# Board.net
KiCad netlist of a schematic drawn in EAGLE
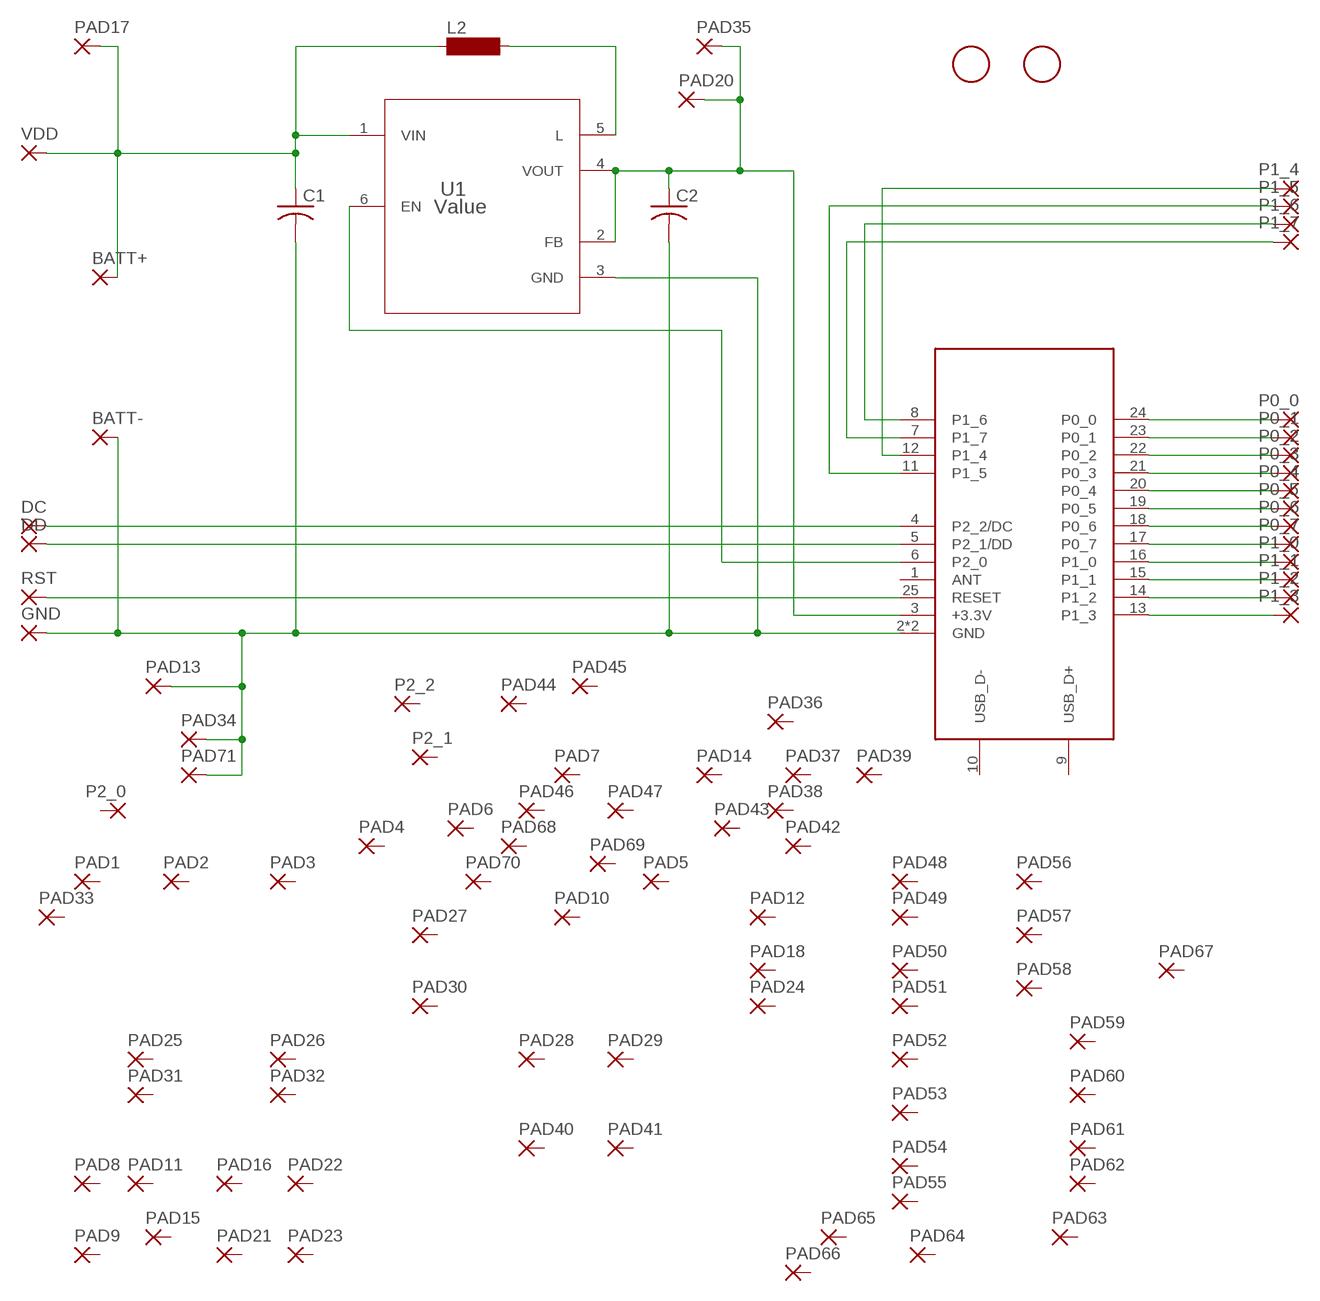
[diagram p0: schematic, sheet 1]

(export (version "E")
  (design (tool "Eeschema 10.0.6"))
  (components
    (comp (ref "BATT+")
      (value "1,6/0,9")
      (footprint "eagle-import:1,6_0,9")
      (libsource (lib "eagle-import") (part "1,6/0,9"))
    )
    (comp (ref "BATT-")
      (value "1,6/0,9")
      (footprint "eagle-import:1,6_0,9")
      (libsource (lib "eagle-import") (part "1,6/0,9"))
    )
    (comp (ref "C1")
      (value "C-USC0603")
      (footprint "eagle-import:C0603")
      (libsource (lib "eagle-import") (part "C-USC0603"))
    )
    (comp (ref "C2")
      (value "C-USC0603")
      (footprint "eagle-import:C0603")
      (libsource (lib "eagle-import") (part "C-USC0603"))
    )
    (comp (ref "DC")
      (value "SMD2")
      (footprint "eagle-import:SMD1,27-2,54")
      (libsource (lib "eagle-import") (part "SMD2"))
    )
    (comp (ref "DD")
      (value "SMD2")
      (footprint "eagle-import:SMD1,27-2,54")
      (libsource (lib "eagle-import") (part "SMD2"))
    )
    (comp (ref "E1")
      (value "CC2540-MODULE-BOARD")
      (footprint "eagle-import:24X15_BOARD")
      (libsource (lib "eagle-import") (part "CC2540-MODULE-BOARD"))
    )
    (comp (ref "GND")
      (value "SMD2")
      (footprint "eagle-import:SMD1,27-2,54")
      (libsource (lib "eagle-import") (part "SMD2"))
    )
    (comp (ref "L2")
      (value "SM-NE29")
      (footprint "eagle-import:SM-NE29")
      (libsource (lib "eagle-import") (part "SM-NE29"))
    )
    (comp (ref "P0_0")
      (value "1,6/0,9")
      (footprint "eagle-import:1,6_0,9")
      (libsource (lib "eagle-import") (part "1,6/0,9"))
    )
    (comp (ref "P0_1")
      (value "1,6/0,9")
      (footprint "eagle-import:1,6_0,9")
      (libsource (lib "eagle-import") (part "1,6/0,9"))
    )
    (comp (ref "P0_2")
      (value "1,6/0,9")
      (footprint "eagle-import:1,6_0,9")
      (libsource (lib "eagle-import") (part "1,6/0,9"))
    )
    (comp (ref "P0_3")
      (value "1,6/0,9")
      (footprint "eagle-import:1,6_0,9")
      (libsource (lib "eagle-import") (part "1,6/0,9"))
    )
    (comp (ref "P0_4")
      (value "1,6/0,9")
      (footprint "eagle-import:1,6_0,9")
      (libsource (lib "eagle-import") (part "1,6/0,9"))
    )
    (comp (ref "P0_5")
      (value "1,6/0,9")
      (footprint "eagle-import:1,6_0,9")
      (libsource (lib "eagle-import") (part "1,6/0,9"))
    )
    (comp (ref "P0_6")
      (value "1,6/0,9")
      (footprint "eagle-import:1,6_0,9")
      (libsource (lib "eagle-import") (part "1,6/0,9"))
    )
    (comp (ref "P0_7")
      (value "1,6/0,9")
      (footprint "eagle-import:1,6_0,9")
      (libsource (lib "eagle-import") (part "1,6/0,9"))
    )
    (comp (ref "P1_0")
      (value "1,6/0,9")
      (footprint "eagle-import:1,6_0,9")
      (libsource (lib "eagle-import") (part "1,6/0,9"))
    )
    (comp (ref "P1_1")
      (value "1,6/0,9")
      (footprint "eagle-import:1,6_0,9")
      (libsource (lib "eagle-import") (part "1,6/0,9"))
    )
    (comp (ref "P1_2")
      (value "1,6/0,9")
      (footprint "eagle-import:1,6_0,9")
      (libsource (lib "eagle-import") (part "1,6/0,9"))
    )
    (comp (ref "P1_3")
      (value "1,6/0,9")
      (footprint "eagle-import:1,6_0,9")
      (libsource (lib "eagle-import") (part "1,6/0,9"))
    )
    (comp (ref "P1_4")
      (value "1,6/0,9")
      (footprint "eagle-import:1,6_0,9")
      (libsource (lib "eagle-import") (part "1,6/0,9"))
    )
    (comp (ref "P1_5")
      (value "1,6/0,9")
      (footprint "eagle-import:1,6_0,9")
      (libsource (lib "eagle-import") (part "1,6/0,9"))
    )
    (comp (ref "P1_6")
      (value "1,6/0,9")
      (footprint "eagle-import:1,6_0,9")
      (libsource (lib "eagle-import") (part "1,6/0,9"))
    )
    (comp (ref "P1_7")
      (value "1,6/0,9")
      (footprint "eagle-import:1,6_0,9")
      (libsource (lib "eagle-import") (part "1,6/0,9"))
    )
    (comp (ref "P2_0")
      (value "1,6/0,9")
      (footprint "eagle-import:1,6_0,9")
      (libsource (lib "eagle-import") (part "1,6/0,9"))
    )
    (comp (ref "P2_1")
      (value "1,6/0,9")
      (footprint "eagle-import:1,6_0,9")
      (libsource (lib "eagle-import") (part "1,6/0,9"))
    )
    (comp (ref "P2_2")
      (value "1,6/0,9")
      (footprint "eagle-import:1,6_0,9")
      (libsource (lib "eagle-import") (part "1,6/0,9"))
    )
    (comp (ref "PAD1")
      (value "1,6/0,9")
      (footprint "eagle-import:1,6_0,9")
      (libsource (lib "eagle-import") (part "1,6/0,9"))
    )
    (comp (ref "PAD2")
      (value "1,6/0,9")
      (footprint "eagle-import:1,6_0,9")
      (libsource (lib "eagle-import") (part "1,6/0,9"))
    )
    (comp (ref "PAD3")
      (value "1,6/0,9")
      (footprint "eagle-import:1,6_0,9")
      (libsource (lib "eagle-import") (part "1,6/0,9"))
    )
    (comp (ref "PAD4")
      (value "1,6/0,9")
      (footprint "eagle-import:1,6_0,9")
      (libsource (lib "eagle-import") (part "1,6/0,9"))
    )
    (comp (ref "PAD5")
      (value "1,6/0,9")
      (footprint "eagle-import:1,6_0,9")
      (libsource (lib "eagle-import") (part "1,6/0,9"))
    )
    (comp (ref "PAD6")
      (value "1,6/0,9")
      (footprint "eagle-import:1,6_0,9")
      (libsource (lib "eagle-import") (part "1,6/0,9"))
    )
    (comp (ref "PAD7")
      (value "1,6/0,9")
      (footprint "eagle-import:1,6_0,9")
      (libsource (lib "eagle-import") (part "1,6/0,9"))
    )
    (comp (ref "PAD8")
      (value "1,6/0,9")
      (footprint "eagle-import:1,6_0,9")
      (libsource (lib "eagle-import") (part "1,6/0,9"))
    )
    (comp (ref "PAD9")
      (value "1,6/0,9")
      (footprint "eagle-import:1,6_0,9")
      (libsource (lib "eagle-import") (part "1,6/0,9"))
    )
    (comp (ref "PAD10")
      (value "1,6/0,9")
      (footprint "eagle-import:1,6_0,9")
      (libsource (lib "eagle-import") (part "1,6/0,9"))
    )
    (comp (ref "PAD11")
      (value "1,6/0,9")
      (footprint "eagle-import:1,6_0,9")
      (libsource (lib "eagle-import") (part "1,6/0,9"))
    )
    (comp (ref "PAD12")
      (value "1,6/0,9")
      (footprint "eagle-import:1,6_0,9")
      (libsource (lib "eagle-import") (part "1,6/0,9"))
    )
    (comp (ref "PAD13")
      (value "1,6/0,9")
      (footprint "eagle-import:1,6_0,9")
      (libsource (lib "eagle-import") (part "1,6/0,9"))
    )
    (comp (ref "PAD14")
      (value "1,6/0,9")
      (footprint "eagle-import:1,6_0,9")
      (libsource (lib "eagle-import") (part "1,6/0,9"))
    )
    (comp (ref "PAD15")
      (value "1,6/0,9")
      (footprint "eagle-import:1,6_0,9")
      (libsource (lib "eagle-import") (part "1,6/0,9"))
    )
    (comp (ref "PAD16")
      (value "1,6/0,9")
      (footprint "eagle-import:1,6_0,9")
      (libsource (lib "eagle-import") (part "1,6/0,9"))
    )
    (comp (ref "PAD17")
      (value "1,6/0,9")
      (footprint "eagle-import:1,6_0,9")
      (libsource (lib "eagle-import") (part "1,6/0,9"))
    )
    (comp (ref "PAD18")
      (value "1,6/0,9")
      (footprint "eagle-import:1,6_0,9")
      (libsource (lib "eagle-import") (part "1,6/0,9"))
    )
    (comp (ref "PAD20")
      (value "1,6/0,9")
      (footprint "eagle-import:1,6_0,9")
      (libsource (lib "eagle-import") (part "1,6/0,9"))
    )
    (comp (ref "PAD21")
      (value "1,6/0,9")
      (footprint "eagle-import:1,6_0,9")
      (libsource (lib "eagle-import") (part "1,6/0,9"))
    )
    (comp (ref "PAD22")
      (value "1,6/0,9")
      (footprint "eagle-import:1,6_0,9")
      (libsource (lib "eagle-import") (part "1,6/0,9"))
    )
    (comp (ref "PAD23")
      (value "1,6/0,9")
      (footprint "eagle-import:1,6_0,9")
      (libsource (lib "eagle-import") (part "1,6/0,9"))
    )
    (comp (ref "PAD24")
      (value "1,6/0,9")
      (footprint "eagle-import:1,6_0,9")
      (libsource (lib "eagle-import") (part "1,6/0,9"))
    )
    (comp (ref "PAD25")
      (value "1,6/0,9")
      (footprint "eagle-import:1,6_0,9")
      (libsource (lib "eagle-import") (part "1,6/0,9"))
    )
    (comp (ref "PAD26")
      (value "1,6/0,9")
      (footprint "eagle-import:1,6_0,9")
      (libsource (lib "eagle-import") (part "1,6/0,9"))
    )
    (comp (ref "PAD27")
      (value "1,6/0,9")
      (footprint "eagle-import:1,6_0,9")
      (libsource (lib "eagle-import") (part "1,6/0,9"))
    )
    (comp (ref "PAD28")
      (value "1,6/0,9")
      (footprint "eagle-import:1,6_0,9")
      (libsource (lib "eagle-import") (part "1,6/0,9"))
    )
    (comp (ref "PAD29")
      (value "1,6/0,9")
      (footprint "eagle-import:1,6_0,9")
      (libsource (lib "eagle-import") (part "1,6/0,9"))
    )
    (comp (ref "PAD30")
      (value "1,6/0,9")
      (footprint "eagle-import:1,6_0,9")
      (libsource (lib "eagle-import") (part "1,6/0,9"))
    )
    (comp (ref "PAD31")
      (value "1,6/0,9")
      (footprint "eagle-import:1,6_0,9")
      (libsource (lib "eagle-import") (part "1,6/0,9"))
    )
    (comp (ref "PAD32")
      (value "1,6/0,9")
      (footprint "eagle-import:1,6_0,9")
      (libsource (lib "eagle-import") (part "1,6/0,9"))
    )
    (comp (ref "PAD33")
      (value "1,6/0,9")
      (footprint "eagle-import:1,6_0,9")
      (libsource (lib "eagle-import") (part "1,6/0,9"))
    )
    (comp (ref "PAD34")
      (value "1,6/0,9")
      (footprint "eagle-import:1,6_0,9")
      (libsource (lib "eagle-import") (part "1,6/0,9"))
    )
    (comp (ref "PAD35")
      (value "1,6/0,9")
      (footprint "eagle-import:1,6_0,9")
      (libsource (lib "eagle-import") (part "1,6/0,9"))
    )
    (comp (ref "PAD36")
      (value "1,6/0,9")
      (footprint "eagle-import:1,6_0,9")
      (libsource (lib "eagle-import") (part "1,6/0,9"))
    )
    (comp (ref "PAD37")
      (value "1,6/0,9")
      (footprint "eagle-import:1,6_0,9")
      (libsource (lib "eagle-import") (part "1,6/0,9"))
    )
    (comp (ref "PAD38")
      (value "1,6/0,9")
      (footprint "eagle-import:1,6_0,9")
      (libsource (lib "eagle-import") (part "1,6/0,9"))
    )
    (comp (ref "PAD39")
      (value "1,6/0,9")
      (footprint "eagle-import:1,6_0,9")
      (libsource (lib "eagle-import") (part "1,6/0,9"))
    )
    (comp (ref "PAD40")
      (value "1,6/0,9")
      (footprint "eagle-import:1,6_0,9")
      (libsource (lib "eagle-import") (part "1,6/0,9"))
    )
    (comp (ref "PAD41")
      (value "1,6/0,9")
      (footprint "eagle-import:1,6_0,9")
      (libsource (lib "eagle-import") (part "1,6/0,9"))
    )
    (comp (ref "PAD42")
      (value "1,6/0,9")
      (footprint "eagle-import:1,6_0,9")
      (libsource (lib "eagle-import") (part "1,6/0,9"))
    )
    (comp (ref "PAD43")
      (value "1,6/0,9")
      (footprint "eagle-import:1,6_0,9")
      (libsource (lib "eagle-import") (part "1,6/0,9"))
    )
    (comp (ref "PAD44")
      (value "1,6/0,9")
      (footprint "eagle-import:1,6_0,9")
      (libsource (lib "eagle-import") (part "1,6/0,9"))
    )
    (comp (ref "PAD45")
      (value "1,6/0,9")
      (footprint "eagle-import:1,6_0,9")
      (libsource (lib "eagle-import") (part "1,6/0,9"))
    )
    (comp (ref "PAD46")
      (value "1,6/0,9")
      (footprint "eagle-import:1,6_0,9")
      (libsource (lib "eagle-import") (part "1,6/0,9"))
    )
    (comp (ref "PAD47")
      (value "1,6/0,9")
      (footprint "eagle-import:1,6_0,9")
      (libsource (lib "eagle-import") (part "1,6/0,9"))
    )
    (comp (ref "PAD48")
      (value "1,6/0,9")
      (footprint "eagle-import:1,6_0,9")
      (libsource (lib "eagle-import") (part "1,6/0,9"))
    )
    (comp (ref "PAD49")
      (value "1,6/0,9")
      (footprint "eagle-import:1,6_0,9")
      (libsource (lib "eagle-import") (part "1,6/0,9"))
    )
    (comp (ref "PAD50")
      (value "1,6/0,9")
      (footprint "eagle-import:1,6_0,9")
      (libsource (lib "eagle-import") (part "1,6/0,9"))
    )
    (comp (ref "PAD51")
      (value "1,6/0,9")
      (footprint "eagle-import:1,6_0,9")
      (libsource (lib "eagle-import") (part "1,6/0,9"))
    )
    (comp (ref "PAD52")
      (value "1,6/0,9")
      (footprint "eagle-import:1,6_0,9")
      (libsource (lib "eagle-import") (part "1,6/0,9"))
    )
    (comp (ref "PAD53")
      (value "1,6/0,9")
      (footprint "eagle-import:1,6_0,9")
      (libsource (lib "eagle-import") (part "1,6/0,9"))
    )
    (comp (ref "PAD54")
      (value "1,6/0,9")
      (footprint "eagle-import:1,6_0,9")
      (libsource (lib "eagle-import") (part "1,6/0,9"))
    )
    (comp (ref "PAD55")
      (value "1,6/0,9")
      (footprint "eagle-import:1,6_0,9")
      (libsource (lib "eagle-import") (part "1,6/0,9"))
    )
    (comp (ref "PAD56")
      (value "1,6/0,9")
      (footprint "eagle-import:1,6_0,9")
      (libsource (lib "eagle-import") (part "1,6/0,9"))
    )
    (comp (ref "PAD57")
      (value "1,6/0,9")
      (footprint "eagle-import:1,6_0,9")
      (libsource (lib "eagle-import") (part "1,6/0,9"))
    )
    (comp (ref "PAD58")
      (value "1,6/0,9")
      (footprint "eagle-import:1,6_0,9")
      (libsource (lib "eagle-import") (part "1,6/0,9"))
    )
    (comp (ref "PAD59")
      (value "1,6/0,9")
      (footprint "eagle-import:1,6_0,9")
      (libsource (lib "eagle-import") (part "1,6/0,9"))
    )
    (comp (ref "PAD60")
      (value "1,6/0,9")
      (footprint "eagle-import:1,6_0,9")
      (libsource (lib "eagle-import") (part "1,6/0,9"))
    )
    (comp (ref "PAD61")
      (value "1,6/0,9")
      (footprint "eagle-import:1,6_0,9")
      (libsource (lib "eagle-import") (part "1,6/0,9"))
    )
    (comp (ref "PAD62")
      (value "1,6/0,9")
      (footprint "eagle-import:1,6_0,9")
      (libsource (lib "eagle-import") (part "1,6/0,9"))
    )
    (comp (ref "PAD63")
      (value "1,6/0,9")
      (footprint "eagle-import:1,6_0,9")
      (libsource (lib "eagle-import") (part "1,6/0,9"))
    )
    (comp (ref "PAD64")
      (value "1,6/0,9")
      (footprint "eagle-import:1,6_0,9")
      (libsource (lib "eagle-import") (part "1,6/0,9"))
    )
    (comp (ref "PAD65")
      (value "1,6/0,9")
      (footprint "eagle-import:1,6_0,9")
      (libsource (lib "eagle-import") (part "1,6/0,9"))
    )
    (comp (ref "PAD66")
      (value "1,6/0,9")
      (footprint "eagle-import:1,6_0,9")
      (libsource (lib "eagle-import") (part "1,6/0,9"))
    )
    (comp (ref "PAD67")
      (value "1,6/0,9")
      (footprint "eagle-import:1,6_0,9")
      (libsource (lib "eagle-import") (part "1,6/0,9"))
    )
    (comp (ref "PAD68")
      (value "1,6/0,9")
      (footprint "eagle-import:1,6_0,9")
      (libsource (lib "eagle-import") (part "1,6/0,9"))
    )
    (comp (ref "PAD69")
      (value "1,6/0,9")
      (footprint "eagle-import:1,6_0,9")
      (libsource (lib "eagle-import") (part "1,6/0,9"))
    )
    (comp (ref "PAD70")
      (value "1,6/0,9")
      (footprint "eagle-import:1,6_0,9")
      (libsource (lib "eagle-import") (part "1,6/0,9"))
    )
    (comp (ref "PAD71")
      (value "1,6/0,9")
      (footprint "eagle-import:1,6_0,9")
      (libsource (lib "eagle-import") (part "1,6/0,9"))
    )
    (comp (ref "RST")
      (value "SMD2")
      (footprint "eagle-import:SMD1,27-2,54")
      (libsource (lib "eagle-import") (part "SMD2"))
    )
    (comp (ref "U$1")
      (value "FIDUCIAL")
      (footprint "eagle-import:FIDUCIAL_1MM")
      (libsource (lib "eagle-import") (part "FIDUCIAL"))
    )
    (comp (ref "U$2")
      (value "FIDUCIAL")
      (footprint "eagle-import:FIDUCIAL_1MM")
      (libsource (lib "eagle-import") (part "FIDUCIAL"))
    )
    (comp (ref "U1")
      (value "Value")
      (footprint "eagle-import:DCK0006A")
      (fields (field (name "MANUFACTURER") "Texas Instruments") (field (name "PARTNUMBER") "TPS61221DCK"))
      (libsource (lib "eagle-import") (part "TPS61221DCKR"))
    )
    (comp (ref "VDD")
      (value "SMD2")
      (footprint "eagle-import:SMD1,27-2,54")
      (libsource (lib "eagle-import") (part "SMD2"))
    )
  )
  (nets
    (net (code "1") (name "Net-(BATT+-P)") (class "Default")
      (node (ref "BATT+") (pin "1") (pinfunction "P_1") (pintype "passive"))
      (node (ref "C1") (pin "1") (pinfunction "1_1") (pintype "passive"))
      (node (ref "L2") (pin "1") (pinfunction "1_1") (pintype "passive"))
      (node (ref "PAD17") (pin "1") (pinfunction "P_1") (pintype "passive"))
      (node (ref "U1") (pin "1") (pinfunction "VIN_1") (pintype "power_in"))
      (node (ref "VDD") (pin "1") (pinfunction "P_1") (pintype "passive"))
    )
    (net (code "2") (name "Net-(BATT--P)") (class "Default")
      (node (ref "BATT-") (pin "1") (pinfunction "P_1") (pintype "passive"))
      (node (ref "C1") (pin "2") (pinfunction "2_2") (pintype "passive"))
      (node (ref "C2") (pin "2") (pinfunction "2_2") (pintype "passive"))
      (node (ref "E1") (pin "2") (pinfunction "GND_2") (pintype "bidirectional"))
      (node (ref "E1") (pin "26") (pinfunction "GND_26") (pintype "bidirectional"))
      (node (ref "GND") (pin "1") (pinfunction "P_1") (pintype "passive"))
      (node (ref "PAD13") (pin "1") (pinfunction "P_1") (pintype "passive"))
      (node (ref "PAD34") (pin "1") (pinfunction "P_1") (pintype "passive"))
      (node (ref "PAD71") (pin "1") (pinfunction "P_1") (pintype "passive"))
      (node (ref "U1") (pin "3") (pinfunction "GND_3") (pintype "power_in"))
    )
    (net (code "3") (name "Net-(DC-P)") (class "Default")
      (node (ref "DC") (pin "1") (pinfunction "P_1") (pintype "passive"))
      (node (ref "E1") (pin "4") (pinfunction "P2_2/DC_4") (pintype "bidirectional"))
    )
    (net (code "4") (name "Net-(DD-P)") (class "Default")
      (node (ref "DD") (pin "1") (pinfunction "P_1") (pintype "passive"))
      (node (ref "E1") (pin "5") (pinfunction "P2_1/DD_5") (pintype "bidirectional"))
    )
    (net (code "5") (name "Net-(E1-+3.3V)") (class "Default")
      (node (ref "C2") (pin "1") (pinfunction "1_1") (pintype "passive"))
      (node (ref "E1") (pin "3") (pinfunction "+3.3V_3") (pintype "bidirectional"))
      (node (ref "PAD20") (pin "1") (pinfunction "P_1") (pintype "passive"))
      (node (ref "PAD35") (pin "1") (pinfunction "P_1") (pintype "passive"))
      (node (ref "U1") (pin "2") (pinfunction "FB_2") (pintype "input"))
      (node (ref "U1") (pin "4") (pinfunction "VOUT_4") (pintype "power_in"))
    )
    (net (code "6") (name "Net-(E1-P0_0)") (class "Default")
      (node (ref "E1") (pin "24") (pinfunction "P0_0_24") (pintype "bidirectional"))
      (node (ref "P0_0") (pin "1") (pinfunction "P_1") (pintype "passive"))
    )
    (net (code "7") (name "Net-(E1-P0_1)") (class "Default")
      (node (ref "E1") (pin "23") (pinfunction "P0_1_23") (pintype "bidirectional"))
      (node (ref "P0_1") (pin "1") (pinfunction "P_1") (pintype "passive"))
    )
    (net (code "8") (name "Net-(E1-P0_2)") (class "Default")
      (node (ref "E1") (pin "22") (pinfunction "P0_2_22") (pintype "bidirectional"))
      (node (ref "P0_2") (pin "1") (pinfunction "P_1") (pintype "passive"))
    )
    (net (code "9") (name "Net-(E1-P0_3)") (class "Default")
      (node (ref "E1") (pin "21") (pinfunction "P0_3_21") (pintype "bidirectional"))
      (node (ref "P0_3") (pin "1") (pinfunction "P_1") (pintype "passive"))
    )
    (net (code "10") (name "Net-(E1-P0_4)") (class "Default")
      (node (ref "E1") (pin "20") (pinfunction "P0_4_20") (pintype "bidirectional"))
      (node (ref "P0_4") (pin "1") (pinfunction "P_1") (pintype "passive"))
    )
    (net (code "11") (name "Net-(E1-P0_5)") (class "Default")
      (node (ref "E1") (pin "19") (pinfunction "P0_5_19") (pintype "bidirectional"))
      (node (ref "P0_5") (pin "1") (pinfunction "P_1") (pintype "passive"))
    )
    (net (code "12") (name "Net-(E1-P0_6)") (class "Default")
      (node (ref "E1") (pin "18") (pinfunction "P0_6_18") (pintype "bidirectional"))
      (node (ref "P0_6") (pin "1") (pinfunction "P_1") (pintype "passive"))
    )
    (net (code "13") (name "Net-(E1-P0_7)") (class "Default")
      (node (ref "E1") (pin "17") (pinfunction "P0_7_17") (pintype "bidirectional"))
      (node (ref "P0_7") (pin "1") (pinfunction "P_1") (pintype "passive"))
    )
    (net (code "14") (name "Net-(E1-P1_0)") (class "Default")
      (node (ref "E1") (pin "16") (pinfunction "P1_0_16") (pintype "bidirectional"))
      (node (ref "P1_0") (pin "1") (pinfunction "P_1") (pintype "passive"))
    )
    (net (code "15") (name "Net-(E1-P1_1)") (class "Default")
      (node (ref "E1") (pin "15") (pinfunction "P1_1_15") (pintype "bidirectional"))
      (node (ref "P1_1") (pin "1") (pinfunction "P_1") (pintype "passive"))
    )
    (net (code "16") (name "Net-(E1-P1_2)") (class "Default")
      (node (ref "E1") (pin "14") (pinfunction "P1_2_14") (pintype "bidirectional"))
      (node (ref "P1_2") (pin "1") (pinfunction "P_1") (pintype "passive"))
    )
    (net (code "17") (name "Net-(E1-P1_3)") (class "Default")
      (node (ref "E1") (pin "13") (pinfunction "P1_3_13") (pintype "bidirectional"))
      (node (ref "P1_3") (pin "1") (pinfunction "P_1") (pintype "passive"))
    )
    (net (code "18") (name "Net-(E1-P1_4)") (class "Default")
      (node (ref "E1") (pin "12") (pinfunction "P1_4_12") (pintype "bidirectional"))
      (node (ref "P1_4") (pin "1") (pinfunction "P_1") (pintype "passive"))
    )
    (net (code "19") (name "Net-(E1-P1_5)") (class "Default")
      (node (ref "E1") (pin "11") (pinfunction "P1_5_11") (pintype "bidirectional"))
      (node (ref "P1_5") (pin "1") (pinfunction "P_1") (pintype "passive"))
    )
    (net (code "20") (name "Net-(E1-P1_6)") (class "Default")
      (node (ref "E1") (pin "8") (pinfunction "P1_6_8") (pintype "bidirectional"))
      (node (ref "P1_6") (pin "1") (pinfunction "P_1") (pintype "passive"))
    )
    (net (code "21") (name "Net-(E1-P1_7)") (class "Default")
      (node (ref "E1") (pin "7") (pinfunction "P1_7_7") (pintype "bidirectional"))
      (node (ref "P1_7") (pin "1") (pinfunction "P_1") (pintype "passive"))
    )
    (net (code "22") (name "Net-(E1-P2_0)") (class "Default")
      (node (ref "E1") (pin "6") (pinfunction "P2_0_6") (pintype "bidirectional"))
      (node (ref "U1") (pin "6") (pinfunction "EN_6") (pintype "input"))
    )
    (net (code "23") (name "Net-(E1-RESET)") (class "Default")
      (node (ref "E1") (pin "25") (pinfunction "RESET_25") (pintype "bidirectional"))
      (node (ref "RST") (pin "1") (pinfunction "P_1") (pintype "passive"))
    )
    (net (code "24") (name "Net-(U1-L)") (class "Default")
      (node (ref "L2") (pin "2") (pinfunction "2_2") (pintype "passive"))
      (node (ref "U1") (pin "5") (pinfunction "L_5") (pintype "passive"))
    )
    (net (code "25") (name "unconnected-(E1-ANT-Pad1)") (class "Default")
      (node (ref "E1") (pin "1") (pinfunction "ANT_1") (pintype "bidirectional"))
    )
    (net (code "26") (name "unconnected-(E1-USB_D+-Pad9)") (class "Default")
      (node (ref "E1") (pin "9") (pinfunction "USB_D+_9") (pintype "bidirectional"))
    )
    (net (code "27") (name "unconnected-(E1-USB_D--Pad10)") (class "Default")
      (node (ref "E1") (pin "10") (pinfunction "USB_D-_10") (pintype "bidirectional"))
    )
    (net (code "28") (name "unconnected-(P2_0-P-Pad1)") (class "Default")
      (node (ref "P2_0") (pin "1") (pinfunction "P_1") (pintype "passive"))
    )
    (net (code "29") (name "unconnected-(P2_1-P-Pad1)") (class "Default")
      (node (ref "P2_1") (pin "1") (pinfunction "P_1") (pintype "passive"))
    )
    (net (code "30") (name "unconnected-(P2_2-P-Pad1)") (class "Default")
      (node (ref "P2_2") (pin "1") (pinfunction "P_1") (pintype "passive"))
    )
    (net (code "31") (name "unconnected-(PAD1-P-Pad1)") (class "Default")
      (node (ref "PAD1") (pin "1") (pinfunction "P_1") (pintype "passive"))
    )
    (net (code "32") (name "unconnected-(PAD2-P-Pad1)") (class "Default")
      (node (ref "PAD2") (pin "1") (pinfunction "P_1") (pintype "passive"))
    )
    (net (code "33") (name "unconnected-(PAD3-P-Pad1)") (class "Default")
      (node (ref "PAD3") (pin "1") (pinfunction "P_1") (pintype "passive"))
    )
    (net (code "34") (name "unconnected-(PAD4-P-Pad1)") (class "Default")
      (node (ref "PAD4") (pin "1") (pinfunction "P_1") (pintype "passive"))
    )
    (net (code "35") (name "unconnected-(PAD5-P-Pad1)") (class "Default")
      (node (ref "PAD5") (pin "1") (pinfunction "P_1") (pintype "passive"))
    )
    (net (code "36") (name "unconnected-(PAD6-P-Pad1)") (class "Default")
      (node (ref "PAD6") (pin "1") (pinfunction "P_1") (pintype "passive"))
    )
    (net (code "37") (name "unconnected-(PAD7-P-Pad1)") (class "Default")
      (node (ref "PAD7") (pin "1") (pinfunction "P_1") (pintype "passive"))
    )
    (net (code "38") (name "unconnected-(PAD8-P-Pad1)") (class "Default")
      (node (ref "PAD8") (pin "1") (pinfunction "P_1") (pintype "passive"))
    )
    (net (code "39") (name "unconnected-(PAD9-P-Pad1)") (class "Default")
      (node (ref "PAD9") (pin "1") (pinfunction "P_1") (pintype "passive"))
    )
    (net (code "40") (name "unconnected-(PAD10-P-Pad1)") (class "Default")
      (node (ref "PAD10") (pin "1") (pinfunction "P_1") (pintype "passive"))
    )
    (net (code "41") (name "unconnected-(PAD11-P-Pad1)") (class "Default")
      (node (ref "PAD11") (pin "1") (pinfunction "P_1") (pintype "passive"))
    )
    (net (code "42") (name "unconnected-(PAD12-P-Pad1)") (class "Default")
      (node (ref "PAD12") (pin "1") (pinfunction "P_1") (pintype "passive"))
    )
    (net (code "43") (name "unconnected-(PAD14-P-Pad1)") (class "Default")
      (node (ref "PAD14") (pin "1") (pinfunction "P_1") (pintype "passive"))
    )
    (net (code "44") (name "unconnected-(PAD15-P-Pad1)") (class "Default")
      (node (ref "PAD15") (pin "1") (pinfunction "P_1") (pintype "passive"))
    )
    (net (code "45") (name "unconnected-(PAD16-P-Pad1)") (class "Default")
      (node (ref "PAD16") (pin "1") (pinfunction "P_1") (pintype "passive"))
    )
    (net (code "46") (name "unconnected-(PAD18-P-Pad1)") (class "Default")
      (node (ref "PAD18") (pin "1") (pinfunction "P_1") (pintype "passive"))
    )
    (net (code "47") (name "unconnected-(PAD21-P-Pad1)") (class "Default")
      (node (ref "PAD21") (pin "1") (pinfunction "P_1") (pintype "passive"))
    )
    (net (code "48") (name "unconnected-(PAD22-P-Pad1)") (class "Default")
      (node (ref "PAD22") (pin "1") (pinfunction "P_1") (pintype "passive"))
    )
    (net (code "49") (name "unconnected-(PAD23-P-Pad1)") (class "Default")
      (node (ref "PAD23") (pin "1") (pinfunction "P_1") (pintype "passive"))
    )
    (net (code "50") (name "unconnected-(PAD24-P-Pad1)") (class "Default")
      (node (ref "PAD24") (pin "1") (pinfunction "P_1") (pintype "passive"))
    )
    (net (code "51") (name "unconnected-(PAD25-P-Pad1)") (class "Default")
      (node (ref "PAD25") (pin "1") (pinfunction "P_1") (pintype "passive"))
    )
    (net (code "52") (name "unconnected-(PAD26-P-Pad1)") (class "Default")
      (node (ref "PAD26") (pin "1") (pinfunction "P_1") (pintype "passive"))
    )
    (net (code "53") (name "unconnected-(PAD27-P-Pad1)") (class "Default")
      (node (ref "PAD27") (pin "1") (pinfunction "P_1") (pintype "passive"))
    )
    (net (code "54") (name "unconnected-(PAD28-P-Pad1)") (class "Default")
      (node (ref "PAD28") (pin "1") (pinfunction "P_1") (pintype "passive"))
    )
    (net (code "55") (name "unconnected-(PAD29-P-Pad1)") (class "Default")
      (node (ref "PAD29") (pin "1") (pinfunction "P_1") (pintype "passive"))
    )
    (net (code "56") (name "unconnected-(PAD30-P-Pad1)") (class "Default")
      (node (ref "PAD30") (pin "1") (pinfunction "P_1") (pintype "passive"))
    )
    (net (code "57") (name "unconnected-(PAD31-P-Pad1)") (class "Default")
      (node (ref "PAD31") (pin "1") (pinfunction "P_1") (pintype "passive"))
    )
    (net (code "58") (name "unconnected-(PAD32-P-Pad1)") (class "Default")
      (node (ref "PAD32") (pin "1") (pinfunction "P_1") (pintype "passive"))
    )
    (net (code "59") (name "unconnected-(PAD33-P-Pad1)") (class "Default")
      (node (ref "PAD33") (pin "1") (pinfunction "P_1") (pintype "passive"))
    )
    (net (code "60") (name "unconnected-(PAD36-P-Pad1)") (class "Default")
      (node (ref "PAD36") (pin "1") (pinfunction "P_1") (pintype "passive"))
    )
    (net (code "61") (name "unconnected-(PAD37-P-Pad1)") (class "Default")
      (node (ref "PAD37") (pin "1") (pinfunction "P_1") (pintype "passive"))
    )
    (net (code "62") (name "unconnected-(PAD38-P-Pad1)") (class "Default")
      (node (ref "PAD38") (pin "1") (pinfunction "P_1") (pintype "passive"))
    )
    (net (code "63") (name "unconnected-(PAD39-P-Pad1)") (class "Default")
      (node (ref "PAD39") (pin "1") (pinfunction "P_1") (pintype "passive"))
    )
    (net (code "64") (name "unconnected-(PAD40-P-Pad1)") (class "Default")
      (node (ref "PAD40") (pin "1") (pinfunction "P_1") (pintype "passive"))
    )
    (net (code "65") (name "unconnected-(PAD41-P-Pad1)") (class "Default")
      (node (ref "PAD41") (pin "1") (pinfunction "P_1") (pintype "passive"))
    )
    (net (code "66") (name "unconnected-(PAD42-P-Pad1)") (class "Default")
      (node (ref "PAD42") (pin "1") (pinfunction "P_1") (pintype "passive"))
    )
    (net (code "67") (name "unconnected-(PAD43-P-Pad1)") (class "Default")
      (node (ref "PAD43") (pin "1") (pinfunction "P_1") (pintype "passive"))
    )
    (net (code "68") (name "unconnected-(PAD44-P-Pad1)") (class "Default")
      (node (ref "PAD44") (pin "1") (pinfunction "P_1") (pintype "passive"))
    )
    (net (code "69") (name "unconnected-(PAD45-P-Pad1)") (class "Default")
      (node (ref "PAD45") (pin "1") (pinfunction "P_1") (pintype "passive"))
    )
    (net (code "70") (name "unconnected-(PAD46-P-Pad1)") (class "Default")
      (node (ref "PAD46") (pin "1") (pinfunction "P_1") (pintype "passive"))
    )
    (net (code "71") (name "unconnected-(PAD47-P-Pad1)") (class "Default")
      (node (ref "PAD47") (pin "1") (pinfunction "P_1") (pintype "passive"))
    )
    (net (code "72") (name "unconnected-(PAD48-P-Pad1)") (class "Default")
      (node (ref "PAD48") (pin "1") (pinfunction "P_1") (pintype "passive"))
    )
    (net (code "73") (name "unconnected-(PAD49-P-Pad1)") (class "Default")
      (node (ref "PAD49") (pin "1") (pinfunction "P_1") (pintype "passive"))
    )
    (net (code "74") (name "unconnected-(PAD50-P-Pad1)") (class "Default")
      (node (ref "PAD50") (pin "1") (pinfunction "P_1") (pintype "passive"))
    )
    (net (code "75") (name "unconnected-(PAD51-P-Pad1)") (class "Default")
      (node (ref "PAD51") (pin "1") (pinfunction "P_1") (pintype "passive"))
    )
    (net (code "76") (name "unconnected-(PAD52-P-Pad1)") (class "Default")
      (node (ref "PAD52") (pin "1") (pinfunction "P_1") (pintype "passive"))
    )
    (net (code "77") (name "unconnected-(PAD53-P-Pad1)") (class "Default")
      (node (ref "PAD53") (pin "1") (pinfunction "P_1") (pintype "passive"))
    )
    (net (code "78") (name "unconnected-(PAD54-P-Pad1)") (class "Default")
      (node (ref "PAD54") (pin "1") (pinfunction "P_1") (pintype "passive"))
    )
    (net (code "79") (name "unconnected-(PAD55-P-Pad1)") (class "Default")
      (node (ref "PAD55") (pin "1") (pinfunction "P_1") (pintype "passive"))
    )
    (net (code "80") (name "unconnected-(PAD56-P-Pad1)") (class "Default")
      (node (ref "PAD56") (pin "1") (pinfunction "P_1") (pintype "passive"))
    )
    (net (code "81") (name "unconnected-(PAD57-P-Pad1)") (class "Default")
      (node (ref "PAD57") (pin "1") (pinfunction "P_1") (pintype "passive"))
    )
    (net (code "82") (name "unconnected-(PAD58-P-Pad1)") (class "Default")
      (node (ref "PAD58") (pin "1") (pinfunction "P_1") (pintype "passive"))
    )
    (net (code "83") (name "unconnected-(PAD59-P-Pad1)") (class "Default")
      (node (ref "PAD59") (pin "1") (pinfunction "P_1") (pintype "passive"))
    )
    (net (code "84") (name "unconnected-(PAD60-P-Pad1)") (class "Default")
      (node (ref "PAD60") (pin "1") (pinfunction "P_1") (pintype "passive"))
    )
    (net (code "85") (name "unconnected-(PAD61-P-Pad1)") (class "Default")
      (node (ref "PAD61") (pin "1") (pinfunction "P_1") (pintype "passive"))
    )
    (net (code "86") (name "unconnected-(PAD62-P-Pad1)") (class "Default")
      (node (ref "PAD62") (pin "1") (pinfunction "P_1") (pintype "passive"))
    )
    (net (code "87") (name "unconnected-(PAD63-P-Pad1)") (class "Default")
      (node (ref "PAD63") (pin "1") (pinfunction "P_1") (pintype "passive"))
    )
    (net (code "88") (name "unconnected-(PAD64-P-Pad1)") (class "Default")
      (node (ref "PAD64") (pin "1") (pinfunction "P_1") (pintype "passive"))
    )
    (net (code "89") (name "unconnected-(PAD65-P-Pad1)") (class "Default")
      (node (ref "PAD65") (pin "1") (pinfunction "P_1") (pintype "passive"))
    )
    (net (code "90") (name "unconnected-(PAD66-P-Pad1)") (class "Default")
      (node (ref "PAD66") (pin "1") (pinfunction "P_1") (pintype "passive"))
    )
    (net (code "91") (name "unconnected-(PAD67-P-Pad1)") (class "Default")
      (node (ref "PAD67") (pin "1") (pinfunction "P_1") (pintype "passive"))
    )
    (net (code "92") (name "unconnected-(PAD68-P-Pad1)") (class "Default")
      (node (ref "PAD68") (pin "1") (pinfunction "P_1") (pintype "passive"))
    )
    (net (code "93") (name "unconnected-(PAD69-P-Pad1)") (class "Default")
      (node (ref "PAD69") (pin "1") (pinfunction "P_1") (pintype "passive"))
    )
    (net (code "94") (name "unconnected-(PAD70-P-Pad1)") (class "Default")
      (node (ref "PAD70") (pin "1") (pinfunction "P_1") (pintype "passive"))
    )
  )
)
